# hall_sensor_test.net
KiCad netlist of a schematic drawn in EAGLE
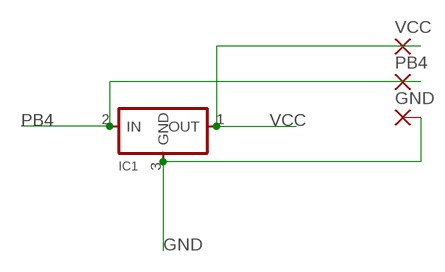
[diagram p0: schematic, sheet 1]

(export (version "E")
  (design (tool "Eeschema 10.0.6"))
  (components
    (comp (ref "GND")
      (value "SMD2")
      (footprint "eagle-import:SMD1,27-2,54")
      (libsource (lib "eagle-import") (part "SMD2"))
    )
    (comp (ref "IC1")
      (value "REGULATORSOT23")
      (footprint "eagle-import:SOT23")
      (libsource (lib "eagle-import") (part "REGULATORSOT23"))
    )
    (comp (ref "PB4")
      (value "SMD2")
      (footprint "eagle-import:SMD1,27-2,54")
      (libsource (lib "eagle-import") (part "SMD2"))
    )
    (comp (ref "VCC")
      (value "SMD2")
      (footprint "eagle-import:SMD1,27-2,54")
      (libsource (lib "eagle-import") (part "SMD2"))
    )
  )
  (nets
    (net (code "1") (name "/GND") (class "Default")
      (node (ref "GND") (pin "1") (pinfunction "P_1") (pintype "passive"))
      (node (ref "IC1") (pin "3") (pinfunction "GND_3") (pintype "bidirectional"))
    )
    (net (code "2") (name "/PB4") (class "Default")
      (node (ref "IC1") (pin "2") (pinfunction "IN_2") (pintype "bidirectional"))
      (node (ref "PB4") (pin "1") (pinfunction "P_1") (pintype "passive"))
    )
    (net (code "3") (name "/VCC") (class "Default")
      (node (ref "IC1") (pin "1") (pinfunction "OUT_1") (pintype "bidirectional"))
      (node (ref "VCC") (pin "1") (pinfunction "P_1") (pintype "passive"))
    )
  )
)
